# dual-dac-w-32-ch-sh.net
KiCad netlist of a schematic drawn in EAGLE
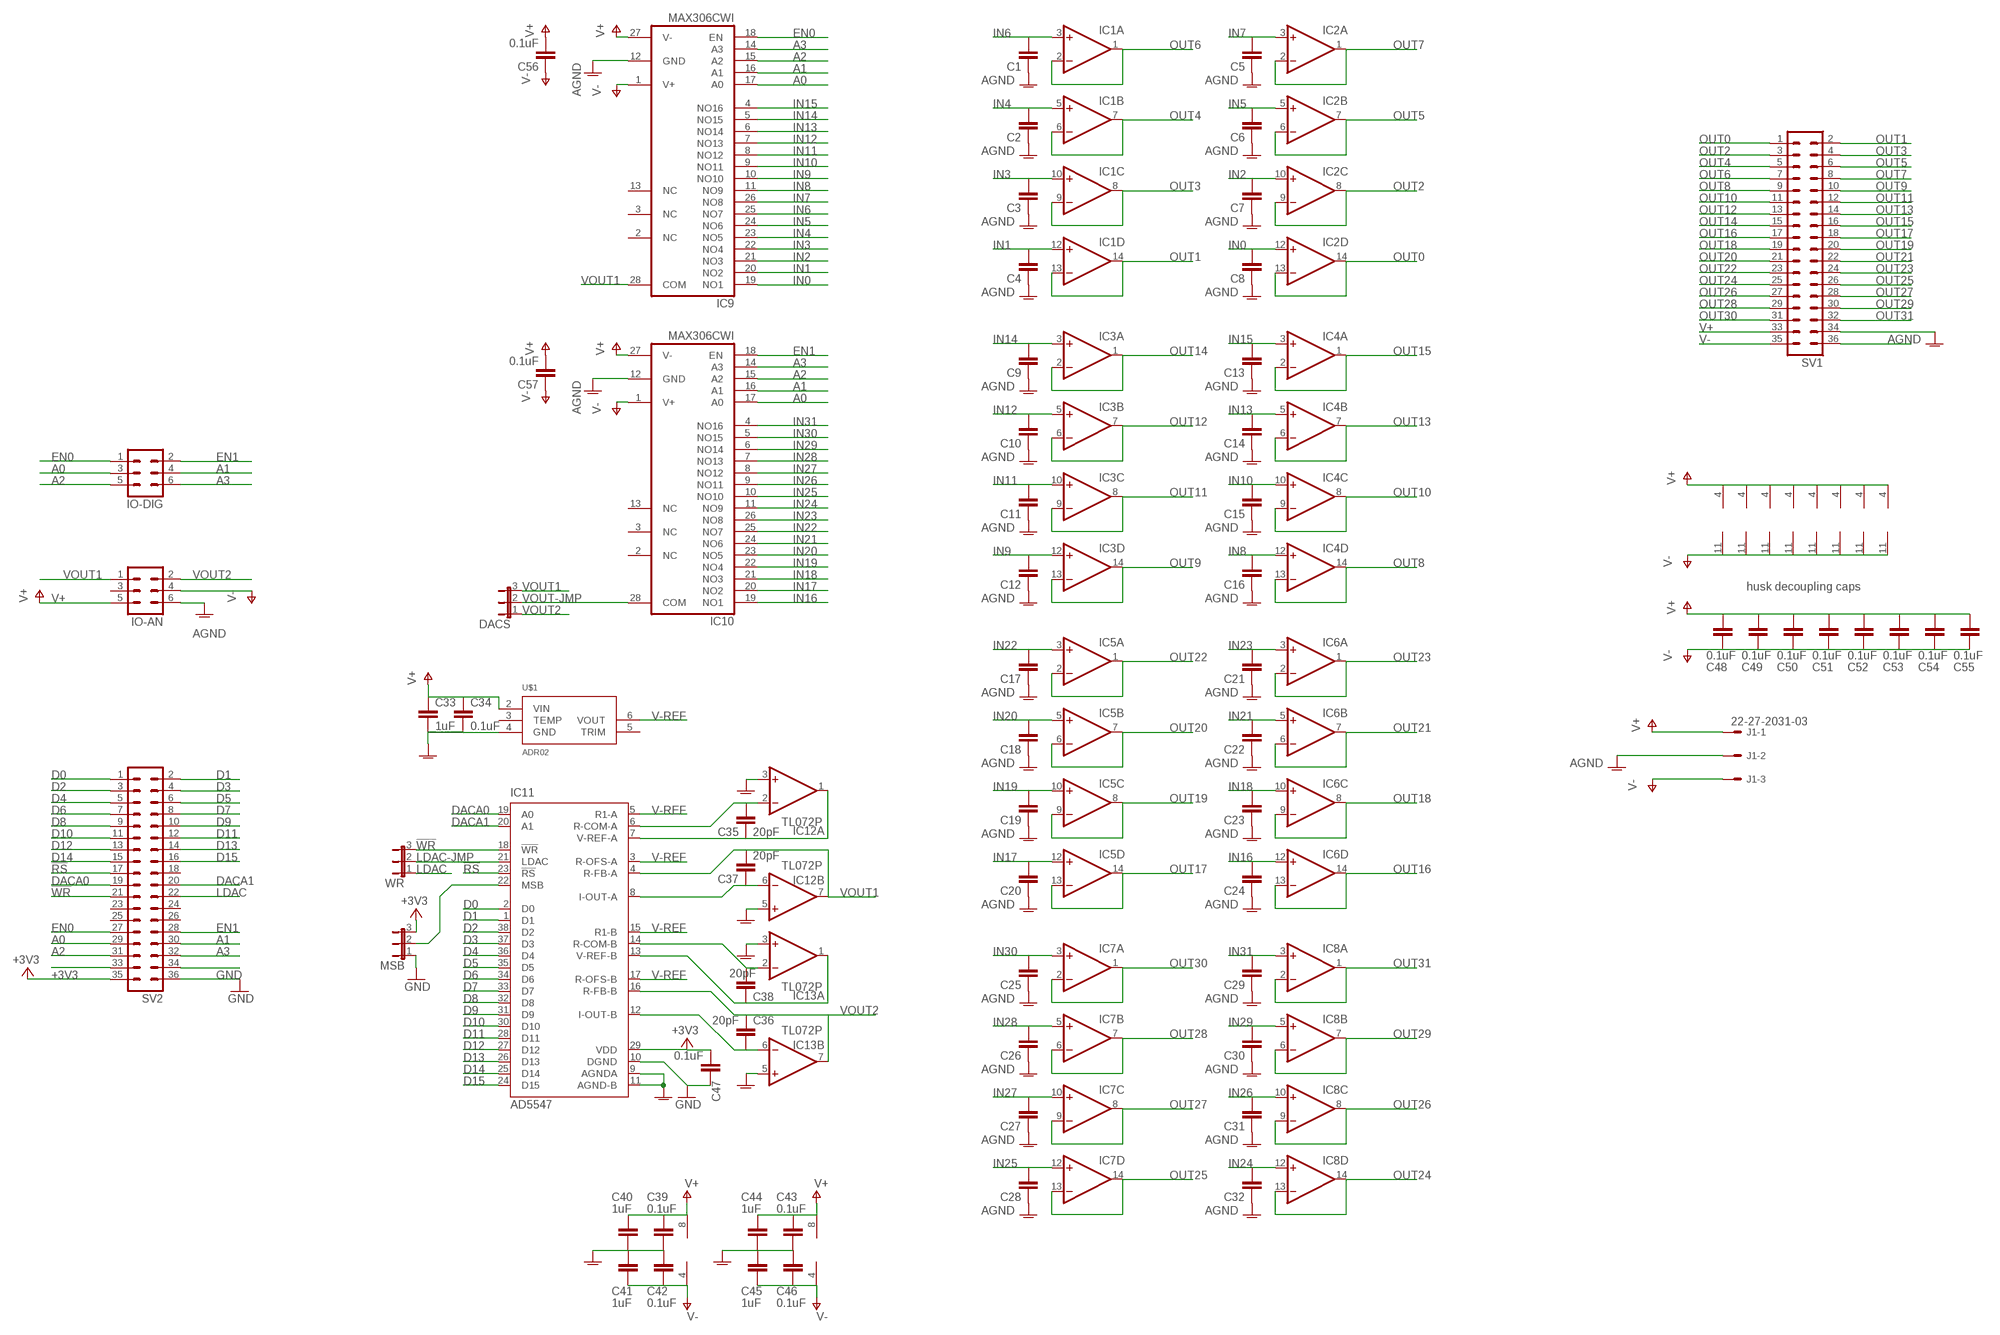
[diagram p0: schematic, sheet 1]

(export (version "E")
  (design (tool "Eeschema 10.0.6"))
  (components
    (comp (ref "C1")
      (value "C-EUC1206")
      (footprint "eagle-import:C1206")
      (libsource (lib "eagle-import") (part "C-EUC1206"))
    )
    (comp (ref "C2")
      (value "C-EUC1206")
      (footprint "eagle-import:C1206")
      (libsource (lib "eagle-import") (part "C-EUC1206"))
    )
    (comp (ref "C3")
      (value "C-EUC1206")
      (footprint "eagle-import:C1206")
      (libsource (lib "eagle-import") (part "C-EUC1206"))
    )
    (comp (ref "C4")
      (value "C-EUC1206")
      (footprint "eagle-import:C1206")
      (libsource (lib "eagle-import") (part "C-EUC1206"))
    )
    (comp (ref "C5")
      (value "C-EUC1206")
      (footprint "eagle-import:C1206")
      (libsource (lib "eagle-import") (part "C-EUC1206"))
    )
    (comp (ref "C6")
      (value "C-EUC1206")
      (footprint "eagle-import:C1206")
      (libsource (lib "eagle-import") (part "C-EUC1206"))
    )
    (comp (ref "C7")
      (value "C-EUC1206")
      (footprint "eagle-import:C1206")
      (libsource (lib "eagle-import") (part "C-EUC1206"))
    )
    (comp (ref "C8")
      (value "C-EUC1206")
      (footprint "eagle-import:C1206")
      (libsource (lib "eagle-import") (part "C-EUC1206"))
    )
    (comp (ref "C9")
      (value "C-EUC1206")
      (footprint "eagle-import:C1206")
      (libsource (lib "eagle-import") (part "C-EUC1206"))
    )
    (comp (ref "C10")
      (value "C-EUC1206")
      (footprint "eagle-import:C1206")
      (libsource (lib "eagle-import") (part "C-EUC1206"))
    )
    (comp (ref "C11")
      (value "C-EUC1206")
      (footprint "eagle-import:C1206")
      (libsource (lib "eagle-import") (part "C-EUC1206"))
    )
    (comp (ref "C12")
      (value "C-EUC1206")
      (footprint "eagle-import:C1206")
      (libsource (lib "eagle-import") (part "C-EUC1206"))
    )
    (comp (ref "C13")
      (value "C-EUC1206")
      (footprint "eagle-import:C1206")
      (libsource (lib "eagle-import") (part "C-EUC1206"))
    )
    (comp (ref "C14")
      (value "C-EUC1206")
      (footprint "eagle-import:C1206")
      (libsource (lib "eagle-import") (part "C-EUC1206"))
    )
    (comp (ref "C15")
      (value "C-EUC1206")
      (footprint "eagle-import:C1206")
      (libsource (lib "eagle-import") (part "C-EUC1206"))
    )
    (comp (ref "C16")
      (value "C-EUC1206")
      (footprint "eagle-import:C1206")
      (libsource (lib "eagle-import") (part "C-EUC1206"))
    )
    (comp (ref "C17")
      (value "C-EUC1206")
      (footprint "eagle-import:C1206")
      (libsource (lib "eagle-import") (part "C-EUC1206"))
    )
    (comp (ref "C18")
      (value "C-EUC1206")
      (footprint "eagle-import:C1206")
      (libsource (lib "eagle-import") (part "C-EUC1206"))
    )
    (comp (ref "C19")
      (value "C-EUC1206")
      (footprint "eagle-import:C1206")
      (libsource (lib "eagle-import") (part "C-EUC1206"))
    )
    (comp (ref "C20")
      (value "C-EUC1206")
      (footprint "eagle-import:C1206")
      (libsource (lib "eagle-import") (part "C-EUC1206"))
    )
    (comp (ref "C21")
      (value "C-EUC1206")
      (footprint "eagle-import:C1206")
      (libsource (lib "eagle-import") (part "C-EUC1206"))
    )
    (comp (ref "C22")
      (value "C-EUC1206")
      (footprint "eagle-import:C1206")
      (libsource (lib "eagle-import") (part "C-EUC1206"))
    )
    (comp (ref "C23")
      (value "C-EUC1206")
      (footprint "eagle-import:C1206")
      (libsource (lib "eagle-import") (part "C-EUC1206"))
    )
    (comp (ref "C24")
      (value "C-EUC1206")
      (footprint "eagle-import:C1206")
      (libsource (lib "eagle-import") (part "C-EUC1206"))
    )
    (comp (ref "C25")
      (value "C-EUC1206")
      (footprint "eagle-import:C1206")
      (libsource (lib "eagle-import") (part "C-EUC1206"))
    )
    (comp (ref "C26")
      (value "C-EUC1206")
      (footprint "eagle-import:C1206")
      (libsource (lib "eagle-import") (part "C-EUC1206"))
    )
    (comp (ref "C27")
      (value "C-EUC1206")
      (footprint "eagle-import:C1206")
      (libsource (lib "eagle-import") (part "C-EUC1206"))
    )
    (comp (ref "C28")
      (value "C-EUC1206")
      (footprint "eagle-import:C1206")
      (libsource (lib "eagle-import") (part "C-EUC1206"))
    )
    (comp (ref "C29")
      (value "C-EUC1206")
      (footprint "eagle-import:C1206")
      (libsource (lib "eagle-import") (part "C-EUC1206"))
    )
    (comp (ref "C30")
      (value "C-EUC1206")
      (footprint "eagle-import:C1206")
      (libsource (lib "eagle-import") (part "C-EUC1206"))
    )
    (comp (ref "C31")
      (value "C-EUC1206")
      (footprint "eagle-import:C1206")
      (libsource (lib "eagle-import") (part "C-EUC1206"))
    )
    (comp (ref "C32")
      (value "C-EUC1206")
      (footprint "eagle-import:C1206")
      (libsource (lib "eagle-import") (part "C-EUC1206"))
    )
    (comp (ref "C33")
      (value "1uF")
      (footprint "eagle-import:C0603")
      (libsource (lib "eagle-import") (part "C-EUC0603"))
    )
    (comp (ref "C34")
      (value "0.1uF")
      (footprint "eagle-import:C0603")
      (libsource (lib "eagle-import") (part "C-EUC0603"))
    )
    (comp (ref "C35")
      (value "20pF")
      (footprint "eagle-import:C0603")
      (libsource (lib "eagle-import") (part "C-EUC0603"))
    )
    (comp (ref "C36")
      (value "20pF")
      (footprint "eagle-import:C0603")
      (libsource (lib "eagle-import") (part "C-EUC0603"))
    )
    (comp (ref "C37")
      (value "20pF")
      (footprint "eagle-import:C0603")
      (libsource (lib "eagle-import") (part "C-EUC0603"))
    )
    (comp (ref "C38")
      (value "20pF")
      (footprint "eagle-import:C0603")
      (libsource (lib "eagle-import") (part "C-EUC0603"))
    )
    (comp (ref "C39")
      (value "0.1uF")
      (footprint "eagle-import:C0603")
      (libsource (lib "eagle-import") (part "C-EUC0603"))
    )
    (comp (ref "C40")
      (value "1uF")
      (footprint "eagle-import:C0603")
      (libsource (lib "eagle-import") (part "C-EUC0603"))
    )
    (comp (ref "C41")
      (value "1uF")
      (footprint "eagle-import:C0603")
      (libsource (lib "eagle-import") (part "C-EUC0603"))
    )
    (comp (ref "C42")
      (value "0.1uF")
      (footprint "eagle-import:C0603")
      (libsource (lib "eagle-import") (part "C-EUC0603"))
    )
    (comp (ref "C43")
      (value "0.1uF")
      (footprint "eagle-import:C0603")
      (libsource (lib "eagle-import") (part "C-EUC0603"))
    )
    (comp (ref "C44")
      (value "1uF")
      (footprint "eagle-import:C0603")
      (libsource (lib "eagle-import") (part "C-EUC0603"))
    )
    (comp (ref "C45")
      (value "1uF")
      (footprint "eagle-import:C0603")
      (libsource (lib "eagle-import") (part "C-EUC0603"))
    )
    (comp (ref "C46")
      (value "0.1uF")
      (footprint "eagle-import:C0603")
      (libsource (lib "eagle-import") (part "C-EUC0603"))
    )
    (comp (ref "C47")
      (value "0.1uF")
      (footprint "eagle-import:C0603")
      (libsource (lib "eagle-import") (part "C-EUC0603"))
    )
    (comp (ref "C48")
      (value "0.1uF")
      (footprint "eagle-import:C0603")
      (libsource (lib "eagle-import") (part "C-EUC0603"))
    )
    (comp (ref "C49")
      (value "0.1uF")
      (footprint "eagle-import:C0603")
      (libsource (lib "eagle-import") (part "C-EUC0603"))
    )
    (comp (ref "C50")
      (value "0.1uF")
      (footprint "eagle-import:C0603")
      (libsource (lib "eagle-import") (part "C-EUC0603"))
    )
    (comp (ref "C51")
      (value "0.1uF")
      (footprint "eagle-import:C0603")
      (libsource (lib "eagle-import") (part "C-EUC0603"))
    )
    (comp (ref "C52")
      (value "0.1uF")
      (footprint "eagle-import:C0603")
      (libsource (lib "eagle-import") (part "C-EUC0603"))
    )
    (comp (ref "C53")
      (value "0.1uF")
      (footprint "eagle-import:C0603")
      (libsource (lib "eagle-import") (part "C-EUC0603"))
    )
    (comp (ref "C54")
      (value "0.1uF")
      (footprint "eagle-import:C0603")
      (libsource (lib "eagle-import") (part "C-EUC0603"))
    )
    (comp (ref "C55")
      (value "0.1uF")
      (footprint "eagle-import:C0603")
      (libsource (lib "eagle-import") (part "C-EUC0603"))
    )
    (comp (ref "C56")
      (value "0.1uF")
      (footprint "eagle-import:C0603")
      (libsource (lib "eagle-import") (part "C-EUC0603"))
    )
    (comp (ref "C57")
      (value "0.1uF")
      (footprint "eagle-import:C0603")
      (libsource (lib "eagle-import") (part "C-EUC0603"))
    )
    (comp (ref "DACS")
      (value "JP2E")
      (footprint "eagle-import:JP2")
      (libsource (lib "eagle-import") (part "JP2E"))
    )
    (comp (ref "IC1")
      (value "TL074D")
      (footprint "eagle-import:SO14")
      (libsource (lib "eagle-import") (part "TL074D"))
    )
    (comp (ref "IC2")
      (value "TL074D")
      (footprint "eagle-import:SO14")
      (libsource (lib "eagle-import") (part "TL074D"))
    )
    (comp (ref "IC3")
      (value "TL074D")
      (footprint "eagle-import:SO14")
      (libsource (lib "eagle-import") (part "TL074D"))
    )
    (comp (ref "IC4")
      (value "TL074D")
      (footprint "eagle-import:SO14")
      (libsource (lib "eagle-import") (part "TL074D"))
    )
    (comp (ref "IC5")
      (value "TL074D")
      (footprint "eagle-import:SO14")
      (libsource (lib "eagle-import") (part "TL074D"))
    )
    (comp (ref "IC6")
      (value "TL074D")
      (footprint "eagle-import:SO14")
      (libsource (lib "eagle-import") (part "TL074D"))
    )
    (comp (ref "IC7")
      (value "TL074D")
      (footprint "eagle-import:SO14")
      (libsource (lib "eagle-import") (part "TL074D"))
    )
    (comp (ref "IC8")
      (value "TL074D")
      (footprint "eagle-import:SO14")
      (libsource (lib "eagle-import") (part "TL074D"))
    )
    (comp (ref "IC9")
      (value "MAX306CWI")
      (footprint "eagle-import:SO28L")
      (fields (field (name "MF") "MAXIM"))
      (libsource (lib "eagle-import") (part "MAX306CWI"))
    )
    (comp (ref "IC10")
      (value "MAX306CWI")
      (footprint "eagle-import:SO28L")
      (fields (field (name "MF") "MAXIM"))
      (libsource (lib "eagle-import") (part "MAX306CWI"))
    )
    (comp (ref "IC11")
      (value "AD5547")
      (footprint "eagle-import:TSSOP38")
      (libsource (lib "eagle-import") (part "AD5547"))
    )
    (comp (ref "IC12")
      (value "TL072P")
      (footprint "eagle-import:DIL08")
      (libsource (lib "eagle-import") (part "TL072P"))
    )
    (comp (ref "IC13")
      (value "TL072P")
      (footprint "eagle-import:DIL08")
      (libsource (lib "eagle-import") (part "TL072P"))
    )
    (comp (ref "IO-AN")
      (value "MA03-2")
      (footprint "eagle-import:MA03-2")
      (libsource (lib "eagle-import") (part "MA03-2"))
    )
    (comp (ref "IO-DIG")
      (value "MA03-2")
      (footprint "eagle-import:MA03-2")
      (libsource (lib "eagle-import") (part "MA03-2"))
    )
    (comp (ref "J1")
      (value "22-27-2031-03")
      (footprint "eagle-import:6410-03")
      (libsource (lib "eagle-import") (part "22-?-0327-2031"))
    )
    (comp (ref "MSB")
      (value "JP2E")
      (footprint "eagle-import:JP2")
      (libsource (lib "eagle-import") (part "JP2E"))
    )
    (comp (ref "SV1")
      (value "MA18-2")
      (footprint "eagle-import:MA18-2")
      (libsource (lib "eagle-import") (part "MA18-2"))
    )
    (comp (ref "SV2")
      (value "MA18-2")
      (footprint "eagle-import:MA18-2")
      (libsource (lib "eagle-import") (part "MA18-2"))
    )
    (comp (ref "U$1")
      (value "ADR02")
      (footprint "eagle-import:SO08")
      (libsource (lib "eagle-import") (part "ADR02"))
    )
    (comp (ref "WR")
      (value "JP2E")
      (footprint "eagle-import:JP2")
      (libsource (lib "eagle-import") (part "JP2E"))
    )
  )
  (nets
    (net (code "1") (name "+3V3") (class "Default")
      (node (ref "C47") (pin "1") (pinfunction "1_1") (pintype "passive"))
      (node (ref "IC11") (pin "29") (pinfunction "VDD_29") (pintype "power_in"))
      (node (ref "MSB") (pin "3") (pinfunction "3_3") (pintype "passive"))
      (node (ref "SV2") (pin "35") (pinfunction "35_35") (pintype "passive"))
    )
    (net (code "2") (name "/A0") (class "Default")
      (node (ref "IC10") (pin "17") (pinfunction "A0_17") (pintype "input"))
      (node (ref "IC9") (pin "17") (pinfunction "A0_17") (pintype "input"))
      (node (ref "IO-DIG") (pin "3") (pinfunction "3_3") (pintype "passive"))
      (node (ref "SV2") (pin "29") (pinfunction "29_29") (pintype "passive"))
    )
    (net (code "3") (name "/A1") (class "Default")
      (node (ref "IC10") (pin "16") (pinfunction "A1_16") (pintype "input"))
      (node (ref "IC9") (pin "16") (pinfunction "A1_16") (pintype "input"))
      (node (ref "IO-DIG") (pin "4") (pinfunction "4_4") (pintype "passive"))
      (node (ref "SV2") (pin "30") (pinfunction "30_30") (pintype "passive"))
    )
    (net (code "4") (name "/A2") (class "Default")
      (node (ref "IC10") (pin "15") (pinfunction "A2_15") (pintype "input"))
      (node (ref "IC9") (pin "15") (pinfunction "A2_15") (pintype "input"))
      (node (ref "IO-DIG") (pin "5") (pinfunction "5_5") (pintype "passive"))
      (node (ref "SV2") (pin "31") (pinfunction "31_31") (pintype "passive"))
    )
    (net (code "5") (name "/A3") (class "Default")
      (node (ref "IC10") (pin "14") (pinfunction "A3_14") (pintype "input"))
      (node (ref "IC9") (pin "14") (pinfunction "A3_14") (pintype "input"))
      (node (ref "IO-DIG") (pin "6") (pinfunction "6_6") (pintype "passive"))
      (node (ref "SV2") (pin "32") (pinfunction "32_32") (pintype "passive"))
    )
    (net (code "6") (name "/D0") (class "Default")
      (node (ref "IC11") (pin "2") (pinfunction "D0_2") (pintype "input"))
      (node (ref "SV2") (pin "1") (pinfunction "1_1") (pintype "passive"))
    )
    (net (code "7") (name "/D1") (class "Default")
      (node (ref "IC11") (pin "1") (pinfunction "D1_1") (pintype "input"))
      (node (ref "SV2") (pin "2") (pinfunction "2_2") (pintype "passive"))
    )
    (net (code "8") (name "/D2") (class "Default")
      (node (ref "IC11") (pin "38") (pinfunction "D2_38") (pintype "input"))
      (node (ref "SV2") (pin "3") (pinfunction "3_3") (pintype "passive"))
    )
    (net (code "9") (name "/D3") (class "Default")
      (node (ref "IC11") (pin "37") (pinfunction "D3_37") (pintype "input"))
      (node (ref "SV2") (pin "4") (pinfunction "4_4") (pintype "passive"))
    )
    (net (code "10") (name "/D4") (class "Default")
      (node (ref "IC11") (pin "36") (pinfunction "D4_36") (pintype "input"))
      (node (ref "SV2") (pin "5") (pinfunction "5_5") (pintype "passive"))
    )
    (net (code "11") (name "/D5") (class "Default")
      (node (ref "IC11") (pin "35") (pinfunction "D5_35") (pintype "input"))
      (node (ref "SV2") (pin "6") (pinfunction "6_6") (pintype "passive"))
    )
    (net (code "12") (name "/D6") (class "Default")
      (node (ref "IC11") (pin "34") (pinfunction "D6_34") (pintype "input"))
      (node (ref "SV2") (pin "7") (pinfunction "7_7") (pintype "passive"))
    )
    (net (code "13") (name "/D7") (class "Default")
      (node (ref "IC11") (pin "33") (pinfunction "D7_33") (pintype "input"))
      (node (ref "SV2") (pin "8") (pinfunction "8_8") (pintype "passive"))
    )
    (net (code "14") (name "/D8") (class "Default")
      (node (ref "IC11") (pin "32") (pinfunction "D8_32") (pintype "input"))
      (node (ref "SV2") (pin "9") (pinfunction "9_9") (pintype "passive"))
    )
    (net (code "15") (name "/D9") (class "Default")
      (node (ref "IC11") (pin "31") (pinfunction "D9_31") (pintype "input"))
      (node (ref "SV2") (pin "10") (pinfunction "10_10") (pintype "passive"))
    )
    (net (code "16") (name "/D10") (class "Default")
      (node (ref "IC11") (pin "30") (pinfunction "D10_30") (pintype "input"))
      (node (ref "SV2") (pin "11") (pinfunction "11_11") (pintype "passive"))
    )
    (net (code "17") (name "/D11") (class "Default")
      (node (ref "IC11") (pin "28") (pinfunction "D11_28") (pintype "input"))
      (node (ref "SV2") (pin "12") (pinfunction "12_12") (pintype "passive"))
    )
    (net (code "18") (name "/D12") (class "Default")
      (node (ref "IC11") (pin "27") (pinfunction "D12_27") (pintype "input"))
      (node (ref "SV2") (pin "13") (pinfunction "13_13") (pintype "passive"))
    )
    (net (code "19") (name "/D13") (class "Default")
      (node (ref "IC11") (pin "26") (pinfunction "D13_26") (pintype "input"))
      (node (ref "SV2") (pin "14") (pinfunction "14_14") (pintype "passive"))
    )
    (net (code "20") (name "/D14") (class "Default")
      (node (ref "IC11") (pin "25") (pinfunction "D14_25") (pintype "input"))
      (node (ref "SV2") (pin "15") (pinfunction "15_15") (pintype "passive"))
    )
    (net (code "21") (name "/D15") (class "Default")
      (node (ref "IC11") (pin "24") (pinfunction "D15_24") (pintype "input"))
      (node (ref "SV2") (pin "16") (pinfunction "16_16") (pintype "passive"))
    )
    (net (code "22") (name "/DACA0") (class "Default")
      (node (ref "IC11") (pin "19") (pinfunction "A0_19") (pintype "input"))
      (node (ref "SV2") (pin "19") (pinfunction "19_19") (pintype "passive"))
    )
    (net (code "23") (name "/DACA1") (class "Default")
      (node (ref "IC11") (pin "20") (pinfunction "A1_20") (pintype "input"))
      (node (ref "SV2") (pin "20") (pinfunction "20_20") (pintype "passive"))
    )
    (net (code "24") (name "/EN0") (class "Default")
      (node (ref "IC9") (pin "18") (pinfunction "EN_18") (pintype "input"))
      (node (ref "IO-DIG") (pin "1") (pinfunction "1_1") (pintype "passive"))
      (node (ref "SV2") (pin "27") (pinfunction "27_27") (pintype "passive"))
    )
    (net (code "25") (name "/EN1") (class "Default")
      (node (ref "IC10") (pin "18") (pinfunction "EN_18") (pintype "input"))
      (node (ref "IO-DIG") (pin "2") (pinfunction "2_2") (pintype "passive"))
      (node (ref "SV2") (pin "28") (pinfunction "28_28") (pintype "passive"))
    )
    (net (code "26") (name "/IN0") (class "Default")
      (node (ref "C8") (pin "2") (pinfunction "2_2") (pintype "passive"))
      (node (ref "IC2") (pin "12") (pinfunction "+IN_12") (pintype "input"))
      (node (ref "IC9") (pin "19") (pinfunction "NO1_19") (pintype "passive"))
    )
    (net (code "27") (name "/IN1") (class "Default")
      (node (ref "C4") (pin "2") (pinfunction "2_2") (pintype "passive"))
      (node (ref "IC1") (pin "12") (pinfunction "+IN_12") (pintype "input"))
      (node (ref "IC9") (pin "20") (pinfunction "NO2_20") (pintype "passive"))
    )
    (net (code "28") (name "/IN2") (class "Default")
      (node (ref "C7") (pin "2") (pinfunction "2_2") (pintype "passive"))
      (node (ref "IC2") (pin "10") (pinfunction "+IN_10") (pintype "input"))
      (node (ref "IC9") (pin "21") (pinfunction "NO3_21") (pintype "passive"))
    )
    (net (code "29") (name "/IN3") (class "Default")
      (node (ref "C3") (pin "2") (pinfunction "2_2") (pintype "passive"))
      (node (ref "IC1") (pin "10") (pinfunction "+IN_10") (pintype "input"))
      (node (ref "IC9") (pin "22") (pinfunction "NO4_22") (pintype "passive"))
    )
    (net (code "30") (name "/IN4") (class "Default")
      (node (ref "C2") (pin "2") (pinfunction "2_2") (pintype "passive"))
      (node (ref "IC1") (pin "5") (pinfunction "+IN_5") (pintype "input"))
      (node (ref "IC9") (pin "23") (pinfunction "NO5_23") (pintype "passive"))
    )
    (net (code "31") (name "/IN5") (class "Default")
      (node (ref "C6") (pin "2") (pinfunction "2_2") (pintype "passive"))
      (node (ref "IC2") (pin "5") (pinfunction "+IN_5") (pintype "input"))
      (node (ref "IC9") (pin "24") (pinfunction "NO6_24") (pintype "passive"))
    )
    (net (code "32") (name "/IN6") (class "Default")
      (node (ref "C1") (pin "2") (pinfunction "2_2") (pintype "passive"))
      (node (ref "IC1") (pin "3") (pinfunction "+IN_3") (pintype "input"))
      (node (ref "IC9") (pin "25") (pinfunction "NO7_25") (pintype "passive"))
    )
    (net (code "33") (name "/IN7") (class "Default")
      (node (ref "C5") (pin "2") (pinfunction "2_2") (pintype "passive"))
      (node (ref "IC2") (pin "3") (pinfunction "+IN_3") (pintype "input"))
      (node (ref "IC9") (pin "26") (pinfunction "NO8_26") (pintype "passive"))
    )
    (net (code "34") (name "/IN8") (class "Default")
      (node (ref "C16") (pin "2") (pinfunction "2_2") (pintype "passive"))
      (node (ref "IC4") (pin "12") (pinfunction "+IN_12") (pintype "input"))
      (node (ref "IC9") (pin "11") (pinfunction "NO9_11") (pintype "passive"))
    )
    (net (code "35") (name "/IN9") (class "Default")
      (node (ref "C12") (pin "2") (pinfunction "2_2") (pintype "passive"))
      (node (ref "IC3") (pin "12") (pinfunction "+IN_12") (pintype "input"))
      (node (ref "IC9") (pin "10") (pinfunction "NO10_10") (pintype "passive"))
    )
    (net (code "36") (name "/IN10") (class "Default")
      (node (ref "C15") (pin "2") (pinfunction "2_2") (pintype "passive"))
      (node (ref "IC4") (pin "10") (pinfunction "+IN_10") (pintype "input"))
      (node (ref "IC9") (pin "9") (pinfunction "NO11_9") (pintype "passive"))
    )
    (net (code "37") (name "/IN11") (class "Default")
      (node (ref "C11") (pin "2") (pinfunction "2_2") (pintype "passive"))
      (node (ref "IC3") (pin "10") (pinfunction "+IN_10") (pintype "input"))
      (node (ref "IC9") (pin "8") (pinfunction "NO12_8") (pintype "passive"))
    )
    (net (code "38") (name "/IN12") (class "Default")
      (node (ref "C10") (pin "2") (pinfunction "2_2") (pintype "passive"))
      (node (ref "IC3") (pin "5") (pinfunction "+IN_5") (pintype "input"))
      (node (ref "IC9") (pin "7") (pinfunction "NO13_7") (pintype "passive"))
    )
    (net (code "39") (name "/IN13") (class "Default")
      (node (ref "C14") (pin "2") (pinfunction "2_2") (pintype "passive"))
      (node (ref "IC4") (pin "5") (pinfunction "+IN_5") (pintype "input"))
      (node (ref "IC9") (pin "6") (pinfunction "NO14_6") (pintype "passive"))
    )
    (net (code "40") (name "/IN14") (class "Default")
      (node (ref "C9") (pin "2") (pinfunction "2_2") (pintype "passive"))
      (node (ref "IC3") (pin "3") (pinfunction "+IN_3") (pintype "input"))
      (node (ref "IC9") (pin "5") (pinfunction "NO15_5") (pintype "passive"))
    )
    (net (code "41") (name "/IN15") (class "Default")
      (node (ref "C13") (pin "2") (pinfunction "2_2") (pintype "passive"))
      (node (ref "IC4") (pin "3") (pinfunction "+IN_3") (pintype "input"))
      (node (ref "IC9") (pin "4") (pinfunction "NO16_4") (pintype "passive"))
    )
    (net (code "42") (name "/IN16") (class "Default")
      (node (ref "C24") (pin "2") (pinfunction "2_2") (pintype "passive"))
      (node (ref "IC10") (pin "19") (pinfunction "NO1_19") (pintype "passive"))
      (node (ref "IC6") (pin "12") (pinfunction "+IN_12") (pintype "input"))
    )
    (net (code "43") (name "/IN17") (class "Default")
      (node (ref "C20") (pin "2") (pinfunction "2_2") (pintype "passive"))
      (node (ref "IC10") (pin "20") (pinfunction "NO2_20") (pintype "passive"))
      (node (ref "IC5") (pin "12") (pinfunction "+IN_12") (pintype "input"))
    )
    (net (code "44") (name "/IN18") (class "Default")
      (node (ref "C23") (pin "2") (pinfunction "2_2") (pintype "passive"))
      (node (ref "IC10") (pin "21") (pinfunction "NO3_21") (pintype "passive"))
      (node (ref "IC6") (pin "10") (pinfunction "+IN_10") (pintype "input"))
    )
    (net (code "45") (name "/IN19") (class "Default")
      (node (ref "C19") (pin "2") (pinfunction "2_2") (pintype "passive"))
      (node (ref "IC10") (pin "22") (pinfunction "NO4_22") (pintype "passive"))
      (node (ref "IC5") (pin "10") (pinfunction "+IN_10") (pintype "input"))
    )
    (net (code "46") (name "/IN20") (class "Default")
      (node (ref "C18") (pin "2") (pinfunction "2_2") (pintype "passive"))
      (node (ref "IC10") (pin "23") (pinfunction "NO5_23") (pintype "passive"))
      (node (ref "IC5") (pin "5") (pinfunction "+IN_5") (pintype "input"))
    )
    (net (code "47") (name "/IN21") (class "Default")
      (node (ref "C22") (pin "2") (pinfunction "2_2") (pintype "passive"))
      (node (ref "IC10") (pin "24") (pinfunction "NO6_24") (pintype "passive"))
      (node (ref "IC6") (pin "5") (pinfunction "+IN_5") (pintype "input"))
    )
    (net (code "48") (name "/IN22") (class "Default")
      (node (ref "C17") (pin "2") (pinfunction "2_2") (pintype "passive"))
      (node (ref "IC10") (pin "25") (pinfunction "NO7_25") (pintype "passive"))
      (node (ref "IC5") (pin "3") (pinfunction "+IN_3") (pintype "input"))
    )
    (net (code "49") (name "/IN23") (class "Default")
      (node (ref "C21") (pin "2") (pinfunction "2_2") (pintype "passive"))
      (node (ref "IC10") (pin "26") (pinfunction "NO8_26") (pintype "passive"))
      (node (ref "IC6") (pin "3") (pinfunction "+IN_3") (pintype "input"))
    )
    (net (code "50") (name "/IN24") (class "Default")
      (node (ref "C32") (pin "2") (pinfunction "2_2") (pintype "passive"))
      (node (ref "IC10") (pin "11") (pinfunction "NO9_11") (pintype "passive"))
      (node (ref "IC8") (pin "12") (pinfunction "+IN_12") (pintype "input"))
    )
    (net (code "51") (name "/IN25") (class "Default")
      (node (ref "C28") (pin "2") (pinfunction "2_2") (pintype "passive"))
      (node (ref "IC10") (pin "10") (pinfunction "NO10_10") (pintype "passive"))
      (node (ref "IC7") (pin "12") (pinfunction "+IN_12") (pintype "input"))
    )
    (net (code "52") (name "/IN26") (class "Default")
      (node (ref "C31") (pin "2") (pinfunction "2_2") (pintype "passive"))
      (node (ref "IC10") (pin "9") (pinfunction "NO11_9") (pintype "passive"))
      (node (ref "IC8") (pin "10") (pinfunction "+IN_10") (pintype "input"))
    )
    (net (code "53") (name "/IN27") (class "Default")
      (node (ref "C27") (pin "2") (pinfunction "2_2") (pintype "passive"))
      (node (ref "IC10") (pin "8") (pinfunction "NO12_8") (pintype "passive"))
      (node (ref "IC7") (pin "10") (pinfunction "+IN_10") (pintype "input"))
    )
    (net (code "54") (name "/IN28") (class "Default")
      (node (ref "C26") (pin "2") (pinfunction "2_2") (pintype "passive"))
      (node (ref "IC10") (pin "7") (pinfunction "NO13_7") (pintype "passive"))
      (node (ref "IC7") (pin "5") (pinfunction "+IN_5") (pintype "input"))
    )
    (net (code "55") (name "/IN29") (class "Default")
      (node (ref "C30") (pin "2") (pinfunction "2_2") (pintype "passive"))
      (node (ref "IC10") (pin "6") (pinfunction "NO14_6") (pintype "passive"))
      (node (ref "IC8") (pin "5") (pinfunction "+IN_5") (pintype "input"))
    )
    (net (code "56") (name "/IN30") (class "Default")
      (node (ref "C25") (pin "2") (pinfunction "2_2") (pintype "passive"))
      (node (ref "IC10") (pin "5") (pinfunction "NO15_5") (pintype "passive"))
      (node (ref "IC7") (pin "3") (pinfunction "+IN_3") (pintype "input"))
    )
    (net (code "57") (name "/IN31") (class "Default")
      (node (ref "C29") (pin "2") (pinfunction "2_2") (pintype "passive"))
      (node (ref "IC10") (pin "4") (pinfunction "NO16_4") (pintype "passive"))
      (node (ref "IC8") (pin "3") (pinfunction "+IN_3") (pintype "input"))
    )
    (net (code "58") (name "/LDAC") (class "Default")
      (node (ref "SV2") (pin "22") (pinfunction "22_22") (pintype "passive"))
      (node (ref "WR") (pin "1") (pinfunction "1_1") (pintype "passive"))
    )
    (net (code "59") (name "/LDAC-JMP") (class "Default")
      (node (ref "IC11") (pin "21") (pinfunction "LDAC_21") (pintype "input"))
      (node (ref "WR") (pin "2") (pinfunction "2_2") (pintype "passive"))
    )
    (net (code "60") (name "/OUT0") (class "Default")
      (node (ref "IC2") (pin "13") (pinfunction "-IN_13") (pintype "input"))
      (node (ref "IC2") (pin "14") (pinfunction "OUT_14") (pintype "output"))
      (node (ref "SV1") (pin "1") (pinfunction "1_1") (pintype "passive"))
    )
    (net (code "61") (name "/OUT1") (class "Default")
      (node (ref "IC1") (pin "13") (pinfunction "-IN_13") (pintype "input"))
      (node (ref "IC1") (pin "14") (pinfunction "OUT_14") (pintype "output"))
      (node (ref "SV1") (pin "2") (pinfunction "2_2") (pintype "passive"))
    )
    (net (code "62") (name "/OUT2") (class "Default")
      (node (ref "IC2") (pin "8") (pinfunction "OUT_8") (pintype "output"))
      (node (ref "IC2") (pin "9") (pinfunction "-IN_9") (pintype "input"))
      (node (ref "SV1") (pin "3") (pinfunction "3_3") (pintype "passive"))
    )
    (net (code "63") (name "/OUT3") (class "Default")
      (node (ref "IC1") (pin "8") (pinfunction "OUT_8") (pintype "output"))
      (node (ref "IC1") (pin "9") (pinfunction "-IN_9") (pintype "input"))
      (node (ref "SV1") (pin "4") (pinfunction "4_4") (pintype "passive"))
    )
    (net (code "64") (name "/OUT4") (class "Default")
      (node (ref "IC1") (pin "6") (pinfunction "-IN_6") (pintype "input"))
      (node (ref "IC1") (pin "7") (pinfunction "OUT_7") (pintype "output"))
      (node (ref "SV1") (pin "5") (pinfunction "5_5") (pintype "passive"))
    )
    (net (code "65") (name "/OUT5") (class "Default")
      (node (ref "IC2") (pin "6") (pinfunction "-IN_6") (pintype "input"))
      (node (ref "IC2") (pin "7") (pinfunction "OUT_7") (pintype "output"))
      (node (ref "SV1") (pin "6") (pinfunction "6_6") (pintype "passive"))
    )
    (net (code "66") (name "/OUT6") (class "Default")
      (node (ref "IC1") (pin "1") (pinfunction "OUT_1") (pintype "output"))
      (node (ref "IC1") (pin "2") (pinfunction "-IN_2") (pintype "input"))
      (node (ref "SV1") (pin "7") (pinfunction "7_7") (pintype "passive"))
    )
    (net (code "67") (name "/OUT7") (class "Default")
      (node (ref "IC2") (pin "1") (pinfunction "OUT_1") (pintype "output"))
      (node (ref "IC2") (pin "2") (pinfunction "-IN_2") (pintype "input"))
      (node (ref "SV1") (pin "8") (pinfunction "8_8") (pintype "passive"))
    )
    (net (code "68") (name "/OUT8") (class "Default")
      (node (ref "IC4") (pin "13") (pinfunction "-IN_13") (pintype "input"))
      (node (ref "IC4") (pin "14") (pinfunction "OUT_14") (pintype "output"))
      (node (ref "SV1") (pin "9") (pinfunction "9_9") (pintype "passive"))
    )
    (net (code "69") (name "/OUT9") (class "Default")
      (node (ref "IC3") (pin "13") (pinfunction "-IN_13") (pintype "input"))
      (node (ref "IC3") (pin "14") (pinfunction "OUT_14") (pintype "output"))
      (node (ref "SV1") (pin "10") (pinfunction "10_10") (pintype "passive"))
    )
    (net (code "70") (name "/OUT10") (class "Default")
      (node (ref "IC4") (pin "8") (pinfunction "OUT_8") (pintype "output"))
      (node (ref "IC4") (pin "9") (pinfunction "-IN_9") (pintype "input"))
      (node (ref "SV1") (pin "11") (pinfunction "11_11") (pintype "passive"))
    )
    (net (code "71") (name "/OUT11") (class "Default")
      (node (ref "IC3") (pin "8") (pinfunction "OUT_8") (pintype "output"))
      (node (ref "IC3") (pin "9") (pinfunction "-IN_9") (pintype "input"))
      (node (ref "SV1") (pin "12") (pinfunction "12_12") (pintype "passive"))
    )
    (net (code "72") (name "/OUT12") (class "Default")
      (node (ref "IC3") (pin "6") (pinfunction "-IN_6") (pintype "input"))
      (node (ref "IC3") (pin "7") (pinfunction "OUT_7") (pintype "output"))
      (node (ref "SV1") (pin "13") (pinfunction "13_13") (pintype "passive"))
    )
    (net (code "73") (name "/OUT13") (class "Default")
      (node (ref "IC4") (pin "6") (pinfunction "-IN_6") (pintype "input"))
      (node (ref "IC4") (pin "7") (pinfunction "OUT_7") (pintype "output"))
      (node (ref "SV1") (pin "14") (pinfunction "14_14") (pintype "passive"))
    )
    (net (code "74") (name "/OUT14") (class "Default")
      (node (ref "IC3") (pin "1") (pinfunction "OUT_1") (pintype "output"))
      (node (ref "IC3") (pin "2") (pinfunction "-IN_2") (pintype "input"))
      (node (ref "SV1") (pin "15") (pinfunction "15_15") (pintype "passive"))
    )
    (net (code "75") (name "/OUT15") (class "Default")
      (node (ref "IC4") (pin "1") (pinfunction "OUT_1") (pintype "output"))
      (node (ref "IC4") (pin "2") (pinfunction "-IN_2") (pintype "input"))
      (node (ref "SV1") (pin "16") (pinfunction "16_16") (pintype "passive"))
    )
    (net (code "76") (name "/OUT16") (class "Default")
      (node (ref "IC6") (pin "13") (pinfunction "-IN_13") (pintype "input"))
      (node (ref "IC6") (pin "14") (pinfunction "OUT_14") (pintype "output"))
      (node (ref "SV1") (pin "17") (pinfunction "17_17") (pintype "passive"))
    )
    (net (code "77") (name "/OUT17") (class "Default")
      (node (ref "IC5") (pin "13") (pinfunction "-IN_13") (pintype "input"))
      (node (ref "IC5") (pin "14") (pinfunction "OUT_14") (pintype "output"))
      (node (ref "SV1") (pin "18") (pinfunction "18_18") (pintype "passive"))
    )
    (net (code "78") (name "/OUT18") (class "Default")
      (node (ref "IC6") (pin "8") (pinfunction "OUT_8") (pintype "output"))
      (node (ref "IC6") (pin "9") (pinfunction "-IN_9") (pintype "input"))
      (node (ref "SV1") (pin "19") (pinfunction "19_19") (pintype "passive"))
    )
    (net (code "79") (name "/OUT19") (class "Default")
      (node (ref "IC5") (pin "8") (pinfunction "OUT_8") (pintype "output"))
      (node (ref "IC5") (pin "9") (pinfunction "-IN_9") (pintype "input"))
      (node (ref "SV1") (pin "20") (pinfunction "20_20") (pintype "passive"))
    )
    (net (code "80") (name "/OUT20") (class "Default")
      (node (ref "IC5") (pin "6") (pinfunction "-IN_6") (pintype "input"))
      (node (ref "IC5") (pin "7") (pinfunction "OUT_7") (pintype "output"))
      (node (ref "SV1") (pin "21") (pinfunction "21_21") (pintype "passive"))
    )
    (net (code "81") (name "/OUT21") (class "Default")
      (node (ref "IC6") (pin "6") (pinfunction "-IN_6") (pintype "input"))
      (node (ref "IC6") (pin "7") (pinfunction "OUT_7") (pintype "output"))
      (node (ref "SV1") (pin "22") (pinfunction "22_22") (pintype "passive"))
    )
    (net (code "82") (name "/OUT22") (class "Default")
      (node (ref "IC5") (pin "1") (pinfunction "OUT_1") (pintype "output"))
      (node (ref "IC5") (pin "2") (pinfunction "-IN_2") (pintype "input"))
      (node (ref "SV1") (pin "23") (pinfunction "23_23") (pintype "passive"))
    )
    (net (code "83") (name "/OUT23") (class "Default")
      (node (ref "IC6") (pin "1") (pinfunction "OUT_1") (pintype "output"))
      (node (ref "IC6") (pin "2") (pinfunction "-IN_2") (pintype "input"))
      (node (ref "SV1") (pin "24") (pinfunction "24_24") (pintype "passive"))
    )
    (net (code "84") (name "/OUT24") (class "Default")
      (node (ref "IC8") (pin "13") (pinfunction "-IN_13") (pintype "input"))
      (node (ref "IC8") (pin "14") (pinfunction "OUT_14") (pintype "output"))
      (node (ref "SV1") (pin "25") (pinfunction "25_25") (pintype "passive"))
    )
    (net (code "85") (name "/OUT25") (class "Default")
      (node (ref "IC7") (pin "13") (pinfunction "-IN_13") (pintype "input"))
      (node (ref "IC7") (pin "14") (pinfunction "OUT_14") (pintype "output"))
      (node (ref "SV1") (pin "26") (pinfunction "26_26") (pintype "passive"))
    )
    (net (code "86") (name "/OUT26") (class "Default")
      (node (ref "IC8") (pin "8") (pinfunction "OUT_8") (pintype "output"))
      (node (ref "IC8") (pin "9") (pinfunction "-IN_9") (pintype "input"))
      (node (ref "SV1") (pin "27") (pinfunction "27_27") (pintype "passive"))
    )
    (net (code "87") (name "/OUT27") (class "Default")
      (node (ref "IC7") (pin "8") (pinfunction "OUT_8") (pintype "output"))
      (node (ref "IC7") (pin "9") (pinfunction "-IN_9") (pintype "input"))
      (node (ref "SV1") (pin "28") (pinfunction "28_28") (pintype "passive"))
    )
    (net (code "88") (name "/OUT28") (class "Default")
      (node (ref "IC7") (pin "6") (pinfunction "-IN_6") (pintype "input"))
      (node (ref "IC7") (pin "7") (pinfunction "OUT_7") (pintype "output"))
      (node (ref "SV1") (pin "29") (pinfunction "29_29") (pintype "passive"))
    )
    (net (code "89") (name "/OUT29") (class "Default")
      (node (ref "IC8") (pin "6") (pinfunction "-IN_6") (pintype "input"))
      (node (ref "IC8") (pin "7") (pinfunction "OUT_7") (pintype "output"))
      (node (ref "SV1") (pin "30") (pinfunction "30_30") (pintype "passive"))
    )
    (net (code "90") (name "/OUT30") (class "Default")
      (node (ref "IC7") (pin "1") (pinfunction "OUT_1") (pintype "output"))
      (node (ref "IC7") (pin "2") (pinfunction "-IN_2") (pintype "input"))
      (node (ref "SV1") (pin "31") (pinfunction "31_31") (pintype "passive"))
    )
    (net (code "91") (name "/OUT31") (class "Default")
      (node (ref "IC8") (pin "1") (pinfunction "OUT_1") (pintype "output"))
      (node (ref "IC8") (pin "2") (pinfunction "-IN_2") (pintype "input"))
      (node (ref "SV1") (pin "32") (pinfunction "32_32") (pintype "passive"))
    )
    (net (code "92") (name "/V-REF") (class "Default")
      (node (ref "IC11") (pin "15") (pinfunction "R1-B_15") (pintype "input"))
      (node (ref "IC11") (pin "17") (pinfunction "R-OFS-B_17") (pintype "input"))
      (node (ref "IC11") (pin "3") (pinfunction "R-OFS-A_3") (pintype "input"))
      (node (ref "IC11") (pin "5") (pinfunction "R1-A_5") (pintype "input"))
      (node (ref "U$1") (pin "6") (pinfunction "VOUT_6") (pintype "output"))
    )
    (net (code "93") (name "/VOUT-JMP") (class "Default")
      (node (ref "DACS") (pin "2") (pinfunction "2_2") (pintype "passive"))
      (node (ref "IC10") (pin "28") (pinfunction "COM_28") (pintype "passive"))
    )
    (net (code "94") (name "/VOUT1") (class "Default")
      (node (ref "C37") (pin "1") (pinfunction "1_1") (pintype "passive"))
      (node (ref "DACS") (pin "3") (pinfunction "3_3") (pintype "passive"))
      (node (ref "IC11") (pin "4") (pinfunction "R-FB-A_4") (pintype "input"))
      (node (ref "IC12") (pin "7") (pinfunction "OUT_7") (pintype "output"))
      (node (ref "IC9") (pin "28") (pinfunction "COM_28") (pintype "passive"))
      (node (ref "IO-AN") (pin "1") (pinfunction "1_1") (pintype "passive"))
    )
    (net (code "95") (name "/VOUT2") (class "Default")
      (node (ref "C36") (pin "1") (pinfunction "1_1") (pintype "passive"))
      (node (ref "DACS") (pin "1") (pinfunction "1_1") (pintype "passive"))
      (node (ref "IC11") (pin "16") (pinfunction "R-FB-B_16") (pintype "input"))
      (node (ref "IC13") (pin "7") (pinfunction "OUT_7") (pintype "output"))
      (node (ref "IO-AN") (pin "2") (pinfunction "2_2") (pintype "passive"))
    )
    (net (code "96") (name "/~{RS}") (class "Default")
      (node (ref "IC11") (pin "23") (pinfunction "~{RS}_23") (pintype "input"))
      (node (ref "SV2") (pin "17") (pinfunction "17_17") (pintype "passive"))
    )
    (net (code "97") (name "/~{WR}") (class "Default")
      (node (ref "IC11") (pin "18") (pinfunction "~{WR}_18") (pintype "input"))
      (node (ref "SV2") (pin "21") (pinfunction "21_21") (pintype "passive"))
      (node (ref "WR") (pin "3") (pinfunction "3_3") (pintype "passive"))
    )
    (net (code "98") (name "AGND") (class "Default")
      (node (ref "C1") (pin "1") (pinfunction "1_1") (pintype "passive"))
      (node (ref "C10") (pin "1") (pinfunction "1_1") (pintype "passive"))
      (node (ref "C11") (pin "1") (pinfunction "1_1") (pintype "passive"))
      (node (ref "C12") (pin "1") (pinfunction "1_1") (pintype "passive"))
      (node (ref "C13") (pin "1") (pinfunction "1_1") (pintype "passive"))
      (node (ref "C14") (pin "1") (pinfunction "1_1") (pintype "passive"))
      (node (ref "C15") (pin "1") (pinfunction "1_1") (pintype "passive"))
      (node (ref "C16") (pin "1") (pinfunction "1_1") (pintype "passive"))
      (node (ref "C17") (pin "1") (pinfunction "1_1") (pintype "passive"))
      (node (ref "C18") (pin "1") (pinfunction "1_1") (pintype "passive"))
      (node (ref "C19") (pin "1") (pinfunction "1_1") (pintype "passive"))
      (node (ref "C2") (pin "1") (pinfunction "1_1") (pintype "passive"))
      (node (ref "C20") (pin "1") (pinfunction "1_1") (pintype "passive"))
      (node (ref "C21") (pin "1") (pinfunction "1_1") (pintype "passive"))
      (node (ref "C22") (pin "1") (pinfunction "1_1") (pintype "passive"))
      (node (ref "C23") (pin "1") (pinfunction "1_1") (pintype "passive"))
      (node (ref "C24") (pin "1") (pinfunction "1_1") (pintype "passive"))
      (node (ref "C25") (pin "1") (pinfunction "1_1") (pintype "passive"))
      (node (ref "C26") (pin "1") (pinfunction "1_1") (pintype "passive"))
      (node (ref "C27") (pin "1") (pinfunction "1_1") (pintype "passive"))
      (node (ref "C28") (pin "1") (pinfunction "1_1") (pintype "passive"))
      (node (ref "C29") (pin "1") (pinfunction "1_1") (pintype "passive"))
      (node (ref "C3") (pin "1") (pinfunction "1_1") (pintype "passive"))
      (node (ref "C30") (pin "1") (pinfunction "1_1") (pintype "passive"))
      (node (ref "C31") (pin "1") (pinfunction "1_1") (pintype "passive"))
      (node (ref "C32") (pin "1") (pinfunction "1_1") (pintype "passive"))
      (node (ref "C33") (pin "2") (pinfunction "2_2") (pintype "passive"))
      (node (ref "C34") (pin "2") (pinfunction "2_2") (pintype "passive"))
      (node (ref "C39") (pin "1") (pinfunction "1_1") (pintype "passive"))
      (node (ref "C4") (pin "1") (pinfunction "1_1") (pintype "passive"))
      (node (ref "C40") (pin "1") (pinfunction "1_1") (pintype "passive"))
      (node (ref "C41") (pin "2") (pinfunction "2_2") (pintype "passive"))
      (node (ref "C42") (pin "2") (pinfunction "2_2") (pintype "passive"))
      (node (ref "C43") (pin "1") (pinfunction "1_1") (pintype "passive"))
      (node (ref "C44") (pin "1") (pinfunction "1_1") (pintype "passive"))
      (node (ref "C45") (pin "2") (pinfunction "2_2") (pintype "passive"))
      (node (ref "C46") (pin "2") (pinfunction "2_2") (pintype "passive"))
      (node (ref "C5") (pin "1") (pinfunction "1_1") (pintype "passive"))
      (node (ref "C6") (pin "1") (pinfunction "1_1") (pintype "passive"))
      (node (ref "C7") (pin "1") (pinfunction "1_1") (pintype "passive"))
      (node (ref "C8") (pin "1") (pinfunction "1_1") (pintype "passive"))
      (node (ref "C9") (pin "1") (pinfunction "1_1") (pintype "passive"))
      (node (ref "IC10") (pin "12") (pinfunction "GND_12") (pintype "power_in"))
      (node (ref "IC11") (pin "11") (pinfunction "AGND-B_11") (pintype "input"))
      (node (ref "IC11") (pin "9") (pinfunction "AGNDA_9") (pintype "input"))
      (node (ref "IC12") (pin "3") (pinfunction "+IN_3") (pintype "input"))
      (node (ref "IC12") (pin "5") (pinfunction "+IN_5") (pintype "input"))
      (node (ref "IC13") (pin "3") (pinfunction "+IN_3") (pintype "input"))
      (node (ref "IC13") (pin "5") (pinfunction "+IN_5") (pintype "input"))
      (node (ref "IC9") (pin "12") (pinfunction "GND_12") (pintype "power_in"))
      (node (ref "IO-AN") (pin "6") (pinfunction "6_6") (pintype "passive"))
      (node (ref "J1") (pin "2") (pinfunction "S_2") (pintype "passive"))
      (node (ref "SV1") (pin "34") (pinfunction "34_34") (pintype "passive"))
      (node (ref "U$1") (pin "4") (pinfunction "GND_4") (pintype "input"))
    )
    (net (code "99") (name "GND") (class "Default")
      (node (ref "C47") (pin "2") (pinfunction "2_2") (pintype "passive"))
      (node (ref "IC11") (pin "10") (pinfunction "DGND_10") (pintype "input"))
      (node (ref "MSB") (pin "1") (pinfunction "1_1") (pintype "passive"))
      (node (ref "SV2") (pin "36") (pinfunction "36_36") (pintype "passive"))
    )
    (net (code "100") (name "Net-(IC11-I-OUT-A)") (class "Default")
      (node (ref "C37") (pin "2") (pinfunction "2_2") (pintype "passive"))
      (node (ref "IC11") (pin "8") (pinfunction "I-OUT-A_8") (pintype "output"))
      (node (ref "IC12") (pin "6") (pinfunction "-IN_6") (pintype "input"))
    )
    (net (code "101") (name "Net-(IC11-I-OUT-B)") (class "Default")
      (node (ref "C36") (pin "2") (pinfunction "2_2") (pintype "passive"))
      (node (ref "IC11") (pin "12") (pinfunction "I-OUT-B_12") (pintype "output"))
      (node (ref "IC13") (pin "6") (pinfunction "-IN_6") (pintype "input"))
    )
    (net (code "102") (name "Net-(IC11-MSB)") (class "Default")
      (node (ref "IC11") (pin "22") (pinfunction "MSB_22") (pintype "input"))
      (node (ref "MSB") (pin "2") (pinfunction "2_2") (pintype "passive"))
    )
    (net (code "103") (name "Net-(IC11-R-COM-A)") (class "Default")
      (node (ref "C35") (pin "2") (pinfunction "2_2") (pintype "passive"))
      (node (ref "IC11") (pin "6") (pinfunction "R-COM-A_6") (pintype "bidirectional"))
      (node (ref "IC12") (pin "2") (pinfunction "-IN_2") (pintype "input"))
    )
    (net (code "104") (name "Net-(IC11-R-COM-B)") (class "Default")
      (node (ref "C38") (pin "2") (pinfunction "2_2") (pintype "passive"))
      (node (ref "IC11") (pin "14") (pinfunction "R-COM-B_14") (pintype "bidirectional"))
      (node (ref "IC13") (pin "2") (pinfunction "-IN_2") (pintype "input"))
    )
    (net (code "105") (name "Net-(IC11-V-REF-A)") (class "Default")
      (node (ref "C35") (pin "1") (pinfunction "1_1") (pintype "passive"))
      (node (ref "IC11") (pin "7") (pinfunction "V-REF-A_7") (pintype "input"))
      (node (ref "IC12") (pin "1") (pinfunction "OUT_1") (pintype "output"))
    )
    (net (code "106") (name "Net-(IC11-V-REF-B)") (class "Default")
      (node (ref "C38") (pin "1") (pinfunction "1_1") (pintype "passive"))
      (node (ref "IC11") (pin "13") (pinfunction "V-REF-B_13") (pintype "input"))
      (node (ref "IC13") (pin "1") (pinfunction "OUT_1") (pintype "output"))
    )
    (net (code "107") (name "V+") (class "Default")
      (node (ref "C33") (pin "1") (pinfunction "1_1") (pintype "passive"))
      (node (ref "C34") (pin "1") (pinfunction "1_1") (pintype "passive"))
      (node (ref "C39") (pin "2") (pinfunction "2_2") (pintype "passive"))
      (node (ref "C40") (pin "2") (pinfunction "2_2") (pintype "passive"))
      (node (ref "C43") (pin "2") (pinfunction "2_2") (pintype "passive"))
      (node (ref "C44") (pin "2") (pinfunction "2_2") (pintype "passive"))
      (node (ref "C48") (pin "2") (pinfunction "2_2") (pintype "passive"))
      (node (ref "C49") (pin "2") (pinfunction "2_2") (pintype "passive"))
      (node (ref "C50") (pin "2") (pinfunction "2_2") (pintype "passive"))
      (node (ref "C51") (pin "2") (pinfunction "2_2") (pintype "passive"))
      (node (ref "C52") (pin "2") (pinfunction "2_2") (pintype "passive"))
      (node (ref "C53") (pin "2") (pinfunction "2_2") (pintype "passive"))
      (node (ref "C54") (pin "2") (pinfunction "2_2") (pintype "passive"))
      (node (ref "C55") (pin "2") (pinfunction "2_2") (pintype "passive"))
      (node (ref "C56") (pin "2") (pinfunction "2_2") (pintype "passive"))
      (node (ref "C57") (pin "2") (pinfunction "2_2") (pintype "passive"))
      (node (ref "IC1") (pin "4") (pinfunction "V+_4") (pintype "power_in"))
      (node (ref "IC10") (pin "27") (pinfunction "V-_27") (pintype "power_in"))
      (node (ref "IC12") (pin "8") (pinfunction "V+_8") (pintype "power_in"))
      (node (ref "IC13") (pin "8") (pinfunction "V+_8") (pintype "power_in"))
      (node (ref "IC2") (pin "4") (pinfunction "V+_4") (pintype "power_in"))
      (node (ref "IC3") (pin "4") (pinfunction "V+_4") (pintype "power_in"))
      (node (ref "IC4") (pin "4") (pinfunction "V+_4") (pintype "power_in"))
      (node (ref "IC5") (pin "4") (pinfunction "V+_4") (pintype "power_in"))
      (node (ref "IC6") (pin "4") (pinfunction "V+_4") (pintype "power_in"))
      (node (ref "IC7") (pin "4") (pinfunction "V+_4") (pintype "power_in"))
      (node (ref "IC8") (pin "4") (pinfunction "V+_4") (pintype "power_in"))
      (node (ref "IC9") (pin "27") (pinfunction "V-_27") (pintype "power_in"))
      (node (ref "IO-AN") (pin "5") (pinfunction "5_5") (pintype "passive"))
      (node (ref "J1") (pin "1") (pinfunction "S_1") (pintype "passive"))
      (node (ref "SV1") (pin "33") (pinfunction "33_33") (pintype "passive"))
      (node (ref "U$1") (pin "2") (pinfunction "VIN_2") (pintype "power_in"))
    )
    (net (code "108") (name "V-") (class "Default")
      (node (ref "C41") (pin "1") (pinfunction "1_1") (pintype "passive"))
      (node (ref "C42") (pin "1") (pinfunction "1_1") (pintype "passive"))
      (node (ref "C45") (pin "1") (pinfunction "1_1") (pintype "passive"))
      (node (ref "C46") (pin "1") (pinfunction "1_1") (pintype "passive"))
      (node (ref "C48") (pin "1") (pinfunction "1_1") (pintype "passive"))
      (node (ref "C49") (pin "1") (pinfunction "1_1") (pintype "passive"))
      (node (ref "C50") (pin "1") (pinfunction "1_1") (pintype "passive"))
      (node (ref "C51") (pin "1") (pinfunction "1_1") (pintype "passive"))
      (node (ref "C52") (pin "1") (pinfunction "1_1") (pintype "passive"))
      (node (ref "C53") (pin "1") (pinfunction "1_1") (pintype "passive"))
      (node (ref "C54") (pin "1") (pinfunction "1_1") (pintype "passive"))
      (node (ref "C55") (pin "1") (pinfunction "1_1") (pintype "passive"))
      (node (ref "C56") (pin "1") (pinfunction "1_1") (pintype "passive"))
      (node (ref "C57") (pin "1") (pinfunction "1_1") (pintype "passive"))
      (node (ref "IC1") (pin "11") (pinfunction "V-_11") (pintype "power_in"))
      (node (ref "IC10") (pin "1") (pinfunction "V+_1") (pintype "power_in"))
      (node (ref "IC12") (pin "4") (pinfunction "V-_4") (pintype "power_in"))
      (node (ref "IC13") (pin "4") (pinfunction "V-_4") (pintype "power_in"))
      (node (ref "IC2") (pin "11") (pinfunction "V-_11") (pintype "power_in"))
      (node (ref "IC3") (pin "11") (pinfunction "V-_11") (pintype "power_in"))
      (node (ref "IC4") (pin "11") (pinfunction "V-_11") (pintype "power_in"))
      (node (ref "IC5") (pin "11") (pinfunction "V-_11") (pintype "power_in"))
      (node (ref "IC6") (pin "11") (pinfunction "V-_11") (pintype "power_in"))
      (node (ref "IC7") (pin "11") (pinfunction "V-_11") (pintype "power_in"))
      (node (ref "IC8") (pin "11") (pinfunction "V-_11") (pintype "power_in"))
      (node (ref "IC9") (pin "1") (pinfunction "V+_1") (pintype "power_in"))
      (node (ref "IO-AN") (pin "4") (pinfunction "4_4") (pintype "passive"))
      (node (ref "J1") (pin "3") (pinfunction "S_3") (pintype "passive"))
      (node (ref "SV1") (pin "35") (pinfunction "35_35") (pintype "passive"))
    )
    (net (code "109") (name "unconnected-(IC9-NC-Pad2)") (class "Default")
      (node (ref "IC9") (pin "2") (pinfunction "NC_2") (pintype "no_connect"))
    )
    (net (code "110") (name "unconnected-(IC9-NC-Pad3)") (class "Default")
      (node (ref "IC9") (pin "3") (pinfunction "NC_3") (pintype "no_connect"))
    )
    (net (code "111") (name "unconnected-(IC9-NC-Pad13)") (class "Default")
      (node (ref "IC9") (pin "13") (pinfunction "NC_13") (pintype "no_connect"))
    )
    (net (code "112") (name "unconnected-(IC10-NC-Pad2)") (class "Default")
      (node (ref "IC10") (pin "2") (pinfunction "NC_2") (pintype "no_connect"))
    )
    (net (code "113") (name "unconnected-(IC10-NC-Pad3)") (class "Default")
      (node (ref "IC10") (pin "3") (pinfunction "NC_3") (pintype "no_connect"))
    )
    (net (code "114") (name "unconnected-(IC10-NC-Pad13)") (class "Default")
      (node (ref "IC10") (pin "13") (pinfunction "NC_13") (pintype "no_connect"))
    )
    (net (code "115") (name "unconnected-(IO-AN-Pad3)") (class "Default")
      (node (ref "IO-AN") (pin "3") (pinfunction "3_3") (pintype "passive"))
    )
    (net (code "116") (name "unconnected-(SV1-Pad36)") (class "Default")
      (node (ref "SV1") (pin "36") (pinfunction "36_36") (pintype "passive"))
    )
    (net (code "117") (name "unconnected-(SV2-Pad18)") (class "Default")
      (node (ref "SV2") (pin "18") (pinfunction "18_18") (pintype "passive"))
    )
    (net (code "118") (name "unconnected-(SV2-Pad23)") (class "Default")
      (node (ref "SV2") (pin "23") (pinfunction "23_23") (pintype "passive"))
    )
    (net (code "119") (name "unconnected-(SV2-Pad24)") (class "Default")
      (node (ref "SV2") (pin "24") (pinfunction "24_24") (pintype "passive"))
    )
    (net (code "120") (name "unconnected-(SV2-Pad25)") (class "Default")
      (node (ref "SV2") (pin "25") (pinfunction "25_25") (pintype "passive"))
    )
    (net (code "121") (name "unconnected-(SV2-Pad26)") (class "Default")
      (node (ref "SV2") (pin "26") (pinfunction "26_26") (pintype "passive"))
    )
    (net (code "122") (name "unconnected-(SV2-Pad33)") (class "Default")
      (node (ref "SV2") (pin "33") (pinfunction "33_33") (pintype "passive"))
    )
    (net (code "123") (name "unconnected-(SV2-Pad34)") (class "Default")
      (node (ref "SV2") (pin "34") (pinfunction "34_34") (pintype "passive"))
    )
    (net (code "124") (name "unconnected-(U$1-TEMP-Pad3)") (class "Default")
      (node (ref "U$1") (pin "3") (pinfunction "TEMP_3") (pintype "input"))
    )
    (net (code "125") (name "unconnected-(U$1-TRIM-Pad5)") (class "Default")
      (node (ref "U$1") (pin "5") (pinfunction "TRIM_5") (pintype "input"))
    )
  )
)
